# MCU.net
KiCad netlist of a schematic drawn in Altium Designer
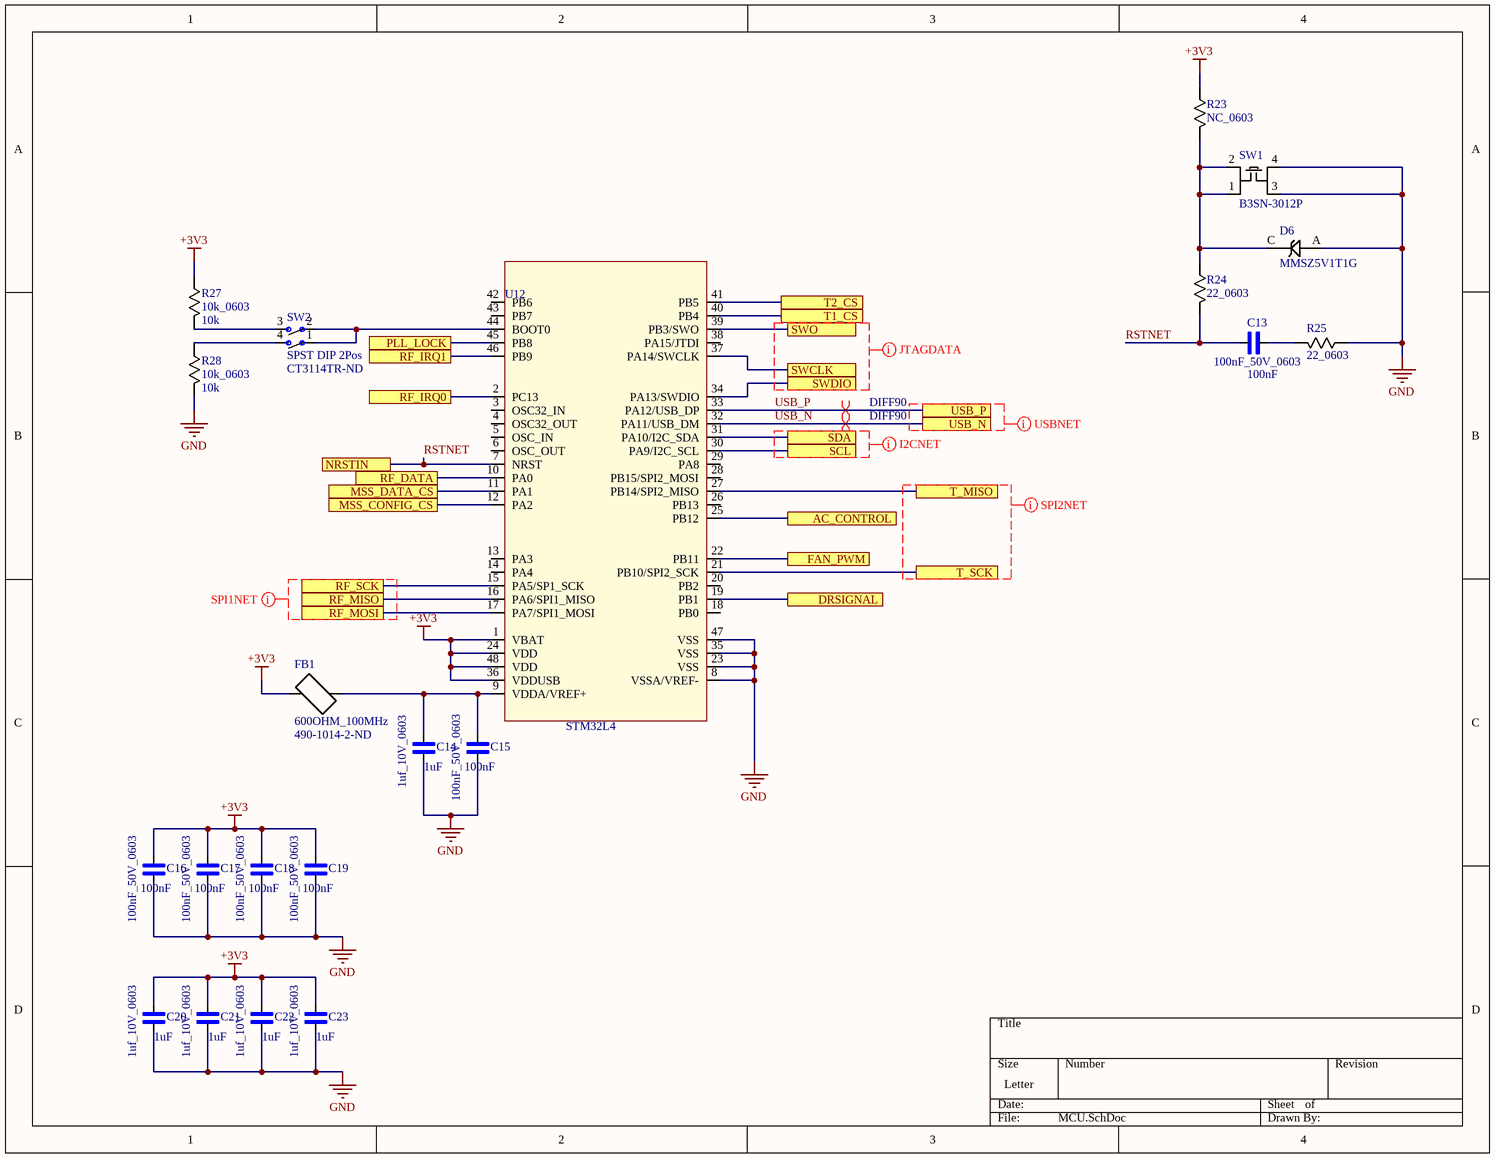
[diagram p0: MCU.SchDoc]

(export (version "E")
  (design (tool "Eeschema 10.0.6"))
  (components
    (comp (ref "C13")
      (value "100nF_50V_0603")
      (footprint "0603")
      (fields
        (field (name "MANUFACTURER") "Murata")
        (field (name "MANUFACTURER PART NUMBER") "GRM188R71H104KA93D")
        (field (name "TOLERANCE") "10%")
        (field (name "CAPACITANCE") "100nF")
      )
      (libsource (lib "Capacitors") (part "100nF_50V_0603"))
    )
    (comp (ref "C14")
      (value "1uf_10V_0603")
      (footprint "0603")
      (fields
        (field (name "MANUFACTURER") "Murata")
        (field (name "MANUFACTURER PART NUMBER") "GRM188R61A105KA61J")
        (field (name "TOLERANCE") "10%")
        (field (name "CAPACITANCE") "1uF")
      )
      (libsource (lib "Capacitors") (part "1uf_10V_0603"))
    )
    (comp (ref "C15")
      (value "100nF_50V_0603")
      (footprint "0603")
      (fields
        (field (name "MANUFACTURER") "Murata")
        (field (name "MANUFACTURER PART NUMBER") "GRM188R71H104KA93D")
        (field (name "TOLERANCE") "10%")
        (field (name "CAPACITANCE") "100nF")
      )
      (libsource (lib "Capacitors") (part "100nF_50V_0603"))
    )
    (comp (ref "C16")
      (value "100nF_50V_0603")
      (footprint "0603")
      (fields
        (field (name "MANUFACTURER") "Murata")
        (field (name "MANUFACTURER PART NUMBER") "GRM188R71H104KA93D")
        (field (name "TOLERANCE") "10%")
        (field (name "CAPACITANCE") "100nF")
      )
      (libsource (lib "Capacitors") (part "100nF_50V_0603"))
    )
    (comp (ref "C17")
      (value "100nF_50V_0603")
      (footprint "0603")
      (fields
        (field (name "MANUFACTURER") "Murata")
        (field (name "MANUFACTURER PART NUMBER") "GRM188R71H104KA93D")
        (field (name "TOLERANCE") "10%")
        (field (name "CAPACITANCE") "100nF")
      )
      (libsource (lib "Capacitors") (part "100nF_50V_0603"))
    )
    (comp (ref "C18")
      (value "100nF_50V_0603")
      (footprint "0603")
      (fields
        (field (name "MANUFACTURER") "Murata")
        (field (name "MANUFACTURER PART NUMBER") "GRM188R71H104KA93D")
        (field (name "TOLERANCE") "10%")
        (field (name "CAPACITANCE") "100nF")
      )
      (libsource (lib "Capacitors") (part "100nF_50V_0603"))
    )
    (comp (ref "C19")
      (value "100nF_50V_0603")
      (footprint "0603")
      (fields
        (field (name "MANUFACTURER") "Murata")
        (field (name "MANUFACTURER PART NUMBER") "GRM188R71H104KA93D")
        (field (name "TOLERANCE") "10%")
        (field (name "CAPACITANCE") "100nF")
      )
      (libsource (lib "Capacitors") (part "100nF_50V_0603"))
    )
    (comp (ref "C20")
      (value "1uf_10V_0603")
      (footprint "0603")
      (fields
        (field (name "MANUFACTURER") "Murata")
        (field (name "MANUFACTURER PART NUMBER") "GRM188R61A105KA61J")
        (field (name "TOLERANCE") "10%")
        (field (name "CAPACITANCE") "1uF")
      )
      (libsource (lib "Capacitors") (part "1uf_10V_0603"))
    )
    (comp (ref "C21")
      (value "1uf_10V_0603")
      (footprint "0603")
      (fields
        (field (name "MANUFACTURER") "Murata")
        (field (name "MANUFACTURER PART NUMBER") "GRM188R61A105KA61J")
        (field (name "TOLERANCE") "10%")
        (field (name "CAPACITANCE") "1uF")
      )
      (libsource (lib "Capacitors") (part "1uf_10V_0603"))
    )
    (comp (ref "C22")
      (value "1uf_10V_0603")
      (footprint "0603")
      (fields
        (field (name "MANUFACTURER") "Murata")
        (field (name "MANUFACTURER PART NUMBER") "GRM188R61A105KA61J")
        (field (name "TOLERANCE") "10%")
        (field (name "CAPACITANCE") "1uF")
      )
      (libsource (lib "Capacitors") (part "1uf_10V_0603"))
    )
    (comp (ref "C23")
      (value "1uf_10V_0603")
      (footprint "0603")
      (fields
        (field (name "MANUFACTURER") "Murata")
        (field (name "MANUFACTURER PART NUMBER") "GRM188R61A105KA61J")
        (field (name "TOLERANCE") "10%")
        (field (name "CAPACITANCE") "1uF")
      )
      (libsource (lib "Capacitors") (part "1uf_10V_0603"))
    )
    (comp (ref "D6")
      (value "MMSZ5V1T1G")
      (footprint "SOIC127P370X94-2N")
      (description "DIODE Zener 5.1V 500mw")
      (fields (field (name "MANUFACTURER") "ON Semiconductor") (field (name "TOLERANCE") "5%"))
      (libsource (lib "Diodes") (part "MMSZ5V1T1G"))
    )
    (comp (ref "FB1")
      (value "600OHM_100MHz")
      (footprint "0603")
      (fields
        (field (name "MANUFACTURER") "Murata")
        (field (name "MANUFACTURER PART NUMBER") "BLM18AG601SN1D")
        (field (name "TOLERANCE") "25%")
        (field (name "SUPPLIER PART NUMBER 1") "490-1014-2-ND")
      )
      (libsource (lib "FerriteBeads") (part "600OHM_100MHz"))
    )
    (comp (ref "R23") (value "NC_0603") (footprint "0603") (libsource (lib "Resistors") (part "NC_0603")))
    (comp (ref "R24")
      (value "22_0603")
      (footprint "0603")
      (fields
        (field (name "MANUFACTURER") "Vishay")
        (field (name "MANUFACTURER PART NUMBER") "CRCW060322R0FKEA")
        (field (name "TOLERANCE") "1%")
      )
      (libsource (lib "Resistors") (part "22_0603"))
    )
    (comp (ref "R25")
      (value "22_0603")
      (footprint "0603")
      (fields
        (field (name "MANUFACTURER") "Vishay")
        (field (name "MANUFACTURER PART NUMBER") "CRCW060322R0FKEA")
        (field (name "TOLERANCE") "1%")
      )
      (libsource (lib "Resistors") (part "22_0603"))
    )
    (comp (ref "R27")
      (value "10k_0603")
      (footprint "0603")
      (fields
        (field (name "MANUFACTURER") "Panasonic")
        (field (name "MANUFACTURER PART NUMBER") "ERJ-3EKF1002V")
        (field (name "TOLERANCE") "1%")
        (field (name "RESISTANCE") "10k")
      )
      (libsource (lib "Resistors") (part "10k_0603"))
    )
    (comp (ref "R28")
      (value "10k_0603")
      (footprint "0603")
      (fields
        (field (name "MANUFACTURER") "Panasonic")
        (field (name "MANUFACTURER PART NUMBER") "ERJ-3EKF1002V")
        (field (name "TOLERANCE") "1%")
        (field (name "RESISTANCE") "10k")
      )
      (libsource (lib "Resistors") (part "10k_0603"))
    )
    (comp (ref "SW1")
      (value "B3SN-3012P")
      (footprint "B3SN-3012P")
      (fields (field (name "MANUFACTURER") "Omron"))
      (libsource (lib "MiscComponents") (part "B3SN-3012P"))
    )
    (comp (ref "SW2")
      (value "SPST DIP 2Pos")
      (footprint "SOP254P990X385-4N")
      (fields
        (field (name "MANUFACTURER") "CTS")
        (field (name "MANUFACTURER PART NUMBER") "219-2MSTR")
        (field (name "SUPPLIER PART NUMBER 1") "CT3114TR-ND")
      )
      (libsource (lib "MiscComponents") (part "SPST DIP 2Pos"))
    )
    (comp (ref "U12")
      (value "STM32L4")
      (footprint "TSQFP50P900X900X160-48N")
      (libsource (lib "MCUs") (part "STM32L433CCTx"))
    )
  )
  (nets
    (net (code "1") (name "+3V3") (class "Default")
      (node (ref "C16") (pin "2") (pinfunction "2_2") (pintype "passive"))
      (node (ref "C17") (pin "2") (pinfunction "2_2") (pintype "passive"))
      (node (ref "C18") (pin "2") (pinfunction "2_2") (pintype "passive"))
      (node (ref "C19") (pin "2") (pinfunction "2_2") (pintype "passive"))
      (node (ref "C20") (pin "2") (pinfunction "2_2") (pintype "passive"))
      (node (ref "C21") (pin "2") (pinfunction "2_2") (pintype "passive"))
      (node (ref "C22") (pin "2") (pinfunction "2_2") (pintype "passive"))
      (node (ref "C23") (pin "2") (pinfunction "2_2") (pintype "passive"))
      (node (ref "FB1") (pin "1") (pintype "passive"))
      (node (ref "R23") (pin "2") (pinfunction "2_2") (pintype "passive"))
      (node (ref "R27") (pin "2") (pinfunction "2_2") (pintype "passive"))
      (node (ref "U12") (pin "1") (pinfunction "VBAT_1") (pintype "passive"))
      (node (ref "U12") (pin "24") (pinfunction "VDD_24") (pintype "passive"))
      (node (ref "U12") (pin "36") (pinfunction "VDDUSB_36") (pintype "passive"))
      (node (ref "U12") (pin "48") (pinfunction "VDD_48") (pintype "passive"))
    )
    (net (code "2") (name "/AC_CONTROL") (class "Default")
      (node (ref "U12") (pin "25") (pinfunction "PB12_25") (pintype "passive"))
    )
    (net (code "3") (name "/DRSIGNAL") (class "Default")
      (node (ref "U12") (pin "19") (pinfunction "PB1_19") (pintype "passive"))
    )
    (net (code "4") (name "/FAN_PWM") (class "Default")
      (node (ref "U12") (pin "22") (pinfunction "PB11_22") (pintype "passive"))
    )
    (net (code "5") (name "/MSS_CONFIG_CS") (class "Default")
      (node (ref "U12") (pin "12") (pinfunction "PA2_12") (pintype "passive"))
    )
    (net (code "6") (name "/MSS_DATA_CS") (class "Default")
      (node (ref "U12") (pin "11") (pinfunction "PA1_11") (pintype "passive"))
    )
    (net (code "7") (name "/PLL_LOCK") (class "Default")
      (node (ref "U12") (pin "45") (pinfunction "PB8_45") (pintype "passive"))
    )
    (net (code "8") (name "/RF_DATA") (class "Default")
      (node (ref "U12") (pin "10") (pinfunction "PA0_10") (pintype "passive"))
    )
    (net (code "9") (name "/RF_IRQ0") (class "Default")
      (node (ref "U12") (pin "2") (pinfunction "PC13_2") (pintype "passive"))
    )
    (net (code "10") (name "/RF_IRQ1") (class "Default")
      (node (ref "U12") (pin "46") (pinfunction "PB9_46") (pintype "passive"))
    )
    (net (code "11") (name "/RF_MISO") (class "Default")
      (node (ref "U12") (pin "16") (pinfunction "PA6/SPI1_MISO_16") (pintype "passive"))
    )
    (net (code "12") (name "/RF_MOSI") (class "Default")
      (node (ref "U12") (pin "17") (pinfunction "PA7/SPI1_MOSI_17") (pintype "passive"))
    )
    (net (code "13") (name "/RF_SCK") (class "Default")
      (node (ref "U12") (pin "15") (pinfunction "PA5/SP1_SCK_15") (pintype "passive"))
    )
    (net (code "14") (name "/RSTNET") (class "Default")
      (node (ref "C13") (pin "1") (pinfunction "1_1") (pintype "passive"))
      (node (ref "R24") (pin "1") (pinfunction "1_1") (pintype "passive"))
      (node (ref "U12") (pin "7") (pinfunction "NRST_7") (pintype "passive"))
    )
    (net (code "15") (name "/SCL") (class "Default")
      (node (ref "U12") (pin "30") (pinfunction "PA9/I2C_SCL_30") (pintype "passive"))
    )
    (net (code "16") (name "/SDA") (class "Default")
      (node (ref "U12") (pin "31") (pinfunction "PA10/I2C_SDA_31") (pintype "passive"))
    )
    (net (code "17") (name "/SWCLK") (class "Default")
      (node (ref "U12") (pin "37") (pinfunction "PA14/SWCLK_37") (pintype "passive"))
    )
    (net (code "18") (name "/SWDIO") (class "Default")
      (node (ref "U12") (pin "34") (pinfunction "PA13/SWDIO_34") (pintype "passive"))
    )
    (net (code "19") (name "/SWO") (class "Default")
      (node (ref "U12") (pin "39") (pinfunction "PB3/SWO_39") (pintype "passive"))
    )
    (net (code "20") (name "/T1_CS") (class "Default")
      (node (ref "U12") (pin "40") (pinfunction "PB4_40") (pintype "passive"))
    )
    (net (code "21") (name "/T2_CS") (class "Default")
      (node (ref "U12") (pin "41") (pinfunction "PB5_41") (pintype "passive"))
    )
    (net (code "22") (name "/T_MISO") (class "Default")
      (node (ref "U12") (pin "27") (pinfunction "PB14/SPI2_MISO_27") (pintype "passive"))
    )
    (net (code "23") (name "/T_SCK") (class "Default")
      (node (ref "U12") (pin "21") (pinfunction "PB10/SPI2_SCK_21") (pintype "passive"))
    )
    (net (code "24") (name "/USB_N") (class "Default")
      (node (ref "U12") (pin "32") (pinfunction "PA11/USB_DM_32") (pintype "passive"))
    )
    (net (code "25") (name "/USB_P") (class "Default")
      (node (ref "U12") (pin "33") (pinfunction "PA12/USB_DP_33") (pintype "passive"))
    )
    (net (code "26") (name "GND") (class "Default")
      (node (ref "C14") (pin "1") (pinfunction "1_1") (pintype "passive"))
      (node (ref "C15") (pin "1") (pinfunction "1_1") (pintype "passive"))
      (node (ref "C16") (pin "1") (pinfunction "1_1") (pintype "passive"))
      (node (ref "C17") (pin "1") (pinfunction "1_1") (pintype "passive"))
      (node (ref "C18") (pin "1") (pinfunction "1_1") (pintype "passive"))
      (node (ref "C19") (pin "1") (pinfunction "1_1") (pintype "passive"))
      (node (ref "C20") (pin "1") (pinfunction "1_1") (pintype "passive"))
      (node (ref "C21") (pin "1") (pinfunction "1_1") (pintype "passive"))
      (node (ref "C22") (pin "1") (pinfunction "1_1") (pintype "passive"))
      (node (ref "C23") (pin "1") (pinfunction "1_1") (pintype "passive"))
      (node (ref "D6") (pin "A") (pintype "passive"))
      (node (ref "R25") (pin "2") (pinfunction "2_2") (pintype "passive"))
      (node (ref "R28") (pin "1") (pinfunction "1_1") (pintype "passive"))
      (node (ref "SW1") (pin "3") (pintype "passive"))
      (node (ref "SW1") (pin "4") (pintype "passive"))
      (node (ref "U12") (pin "23") (pinfunction "VSS_23") (pintype "passive"))
      (node (ref "U12") (pin "35") (pinfunction "VSS_35") (pintype "passive"))
      (node (ref "U12") (pin "47") (pinfunction "VSS_47") (pintype "passive"))
      (node (ref "U12") (pin "8") (pinfunction "VSSA/VREF-_8") (pintype "passive"))
    )
    (net (code "27") (name "Net-(C13-Pad2)") (class "Default")
      (node (ref "C13") (pin "2") (pinfunction "2_2") (pintype "passive"))
      (node (ref "R25") (pin "1") (pinfunction "1_1") (pintype "passive"))
    )
    (net (code "28") (name "Net-(D6-PadC)") (class "Default")
      (node (ref "D6") (pin "C") (pintype "passive"))
      (node (ref "R23") (pin "1") (pinfunction "1_1") (pintype "passive"))
      (node (ref "R24") (pin "2") (pinfunction "2_2") (pintype "passive"))
      (node (ref "SW1") (pin "1") (pintype "passive"))
      (node (ref "SW1") (pin "2") (pintype "passive"))
    )
    (net (code "29") (name "Net-(R27-Pad1)") (class "Default")
      (node (ref "R27") (pin "1") (pinfunction "1_1") (pintype "passive"))
      (node (ref "SW2") (pin "3") (pinfunction "4_3") (pintype "passive"))
    )
    (net (code "30") (name "Net-(R28-Pad2)") (class "Default")
      (node (ref "R28") (pin "2") (pinfunction "2_2") (pintype "passive"))
      (node (ref "SW2") (pin "4") (pinfunction "4_4") (pintype "passive"))
    )
    (net (code "31") (name "Net-(U12-BOOT0)") (class "Default")
      (node (ref "SW2") (pin "1") (pinfunction "1_1") (pintype "passive"))
      (node (ref "SW2") (pin "2") (pinfunction "2_2") (pintype "passive"))
      (node (ref "U12") (pin "44") (pinfunction "BOOT0_44") (pintype "passive"))
    )
    (net (code "32") (name "Net-(U12-VDDA{slash}VREF+)") (class "Default")
      (node (ref "C14") (pin "2") (pinfunction "2_2") (pintype "passive"))
      (node (ref "C15") (pin "2") (pinfunction "2_2") (pintype "passive"))
      (node (ref "FB1") (pin "2") (pintype "passive"))
      (node (ref "U12") (pin "9") (pinfunction "VDDA/VREF+_9") (pintype "passive"))
    )
    (net (code "33") (name "unconnected-(U12-OSC32_IN-Pad3)") (class "Default")
      (node (ref "U12") (pin "3") (pinfunction "OSC32_IN_3") (pintype "passive"))
    )
    (net (code "34") (name "unconnected-(U12-OSC32_OUT-Pad4)") (class "Default")
      (node (ref "U12") (pin "4") (pinfunction "OSC32_OUT_4") (pintype "passive"))
    )
    (net (code "35") (name "unconnected-(U12-OSC_IN-Pad5)") (class "Default")
      (node (ref "U12") (pin "5") (pinfunction "OSC_IN_5") (pintype "passive"))
    )
    (net (code "36") (name "unconnected-(U12-OSC_OUT-Pad6)") (class "Default")
      (node (ref "U12") (pin "6") (pinfunction "OSC_OUT_6") (pintype "passive"))
    )
    (net (code "37") (name "unconnected-(U12-PA3-Pad13)") (class "Default")
      (node (ref "U12") (pin "13") (pinfunction "PA3_13") (pintype "passive"))
    )
    (net (code "38") (name "unconnected-(U12-PA4-Pad14)") (class "Default")
      (node (ref "U12") (pin "14") (pinfunction "PA4_14") (pintype "passive"))
    )
    (net (code "39") (name "unconnected-(U12-PA8-Pad29)") (class "Default")
      (node (ref "U12") (pin "29") (pinfunction "PA8_29") (pintype "passive"))
    )
    (net (code "40") (name "unconnected-(U12-PA15{slash}JTDI-Pad38)") (class "Default")
      (node (ref "U12") (pin "38") (pinfunction "PA15/JTDI_38") (pintype "passive"))
    )
    (net (code "41") (name "unconnected-(U12-PB0-Pad18)") (class "Default")
      (node (ref "U12") (pin "18") (pinfunction "PB0_18") (pintype "passive"))
    )
    (net (code "42") (name "unconnected-(U12-PB2-Pad20)") (class "Default")
      (node (ref "U12") (pin "20") (pinfunction "PB2_20") (pintype "passive"))
    )
    (net (code "43") (name "unconnected-(U12-PB6-Pad42)") (class "Default")
      (node (ref "U12") (pin "42") (pinfunction "PB6_42") (pintype "passive"))
    )
    (net (code "44") (name "unconnected-(U12-PB7-Pad43)") (class "Default")
      (node (ref "U12") (pin "43") (pinfunction "PB7_43") (pintype "passive"))
    )
    (net (code "45") (name "unconnected-(U12-PB13-Pad26)") (class "Default")
      (node (ref "U12") (pin "26") (pinfunction "PB13_26") (pintype "passive"))
    )
    (net (code "46") (name "unconnected-(U12-PB15{slash}SPI2_MOSI-Pad28)") (class "Default")
      (node (ref "U12") (pin "28") (pinfunction "PB15/SPI2_MOSI_28") (pintype "passive"))
    )
  )
)
